# DMFX-2_v1_0.net
KiCad netlist of a schematic drawn in EAGLE
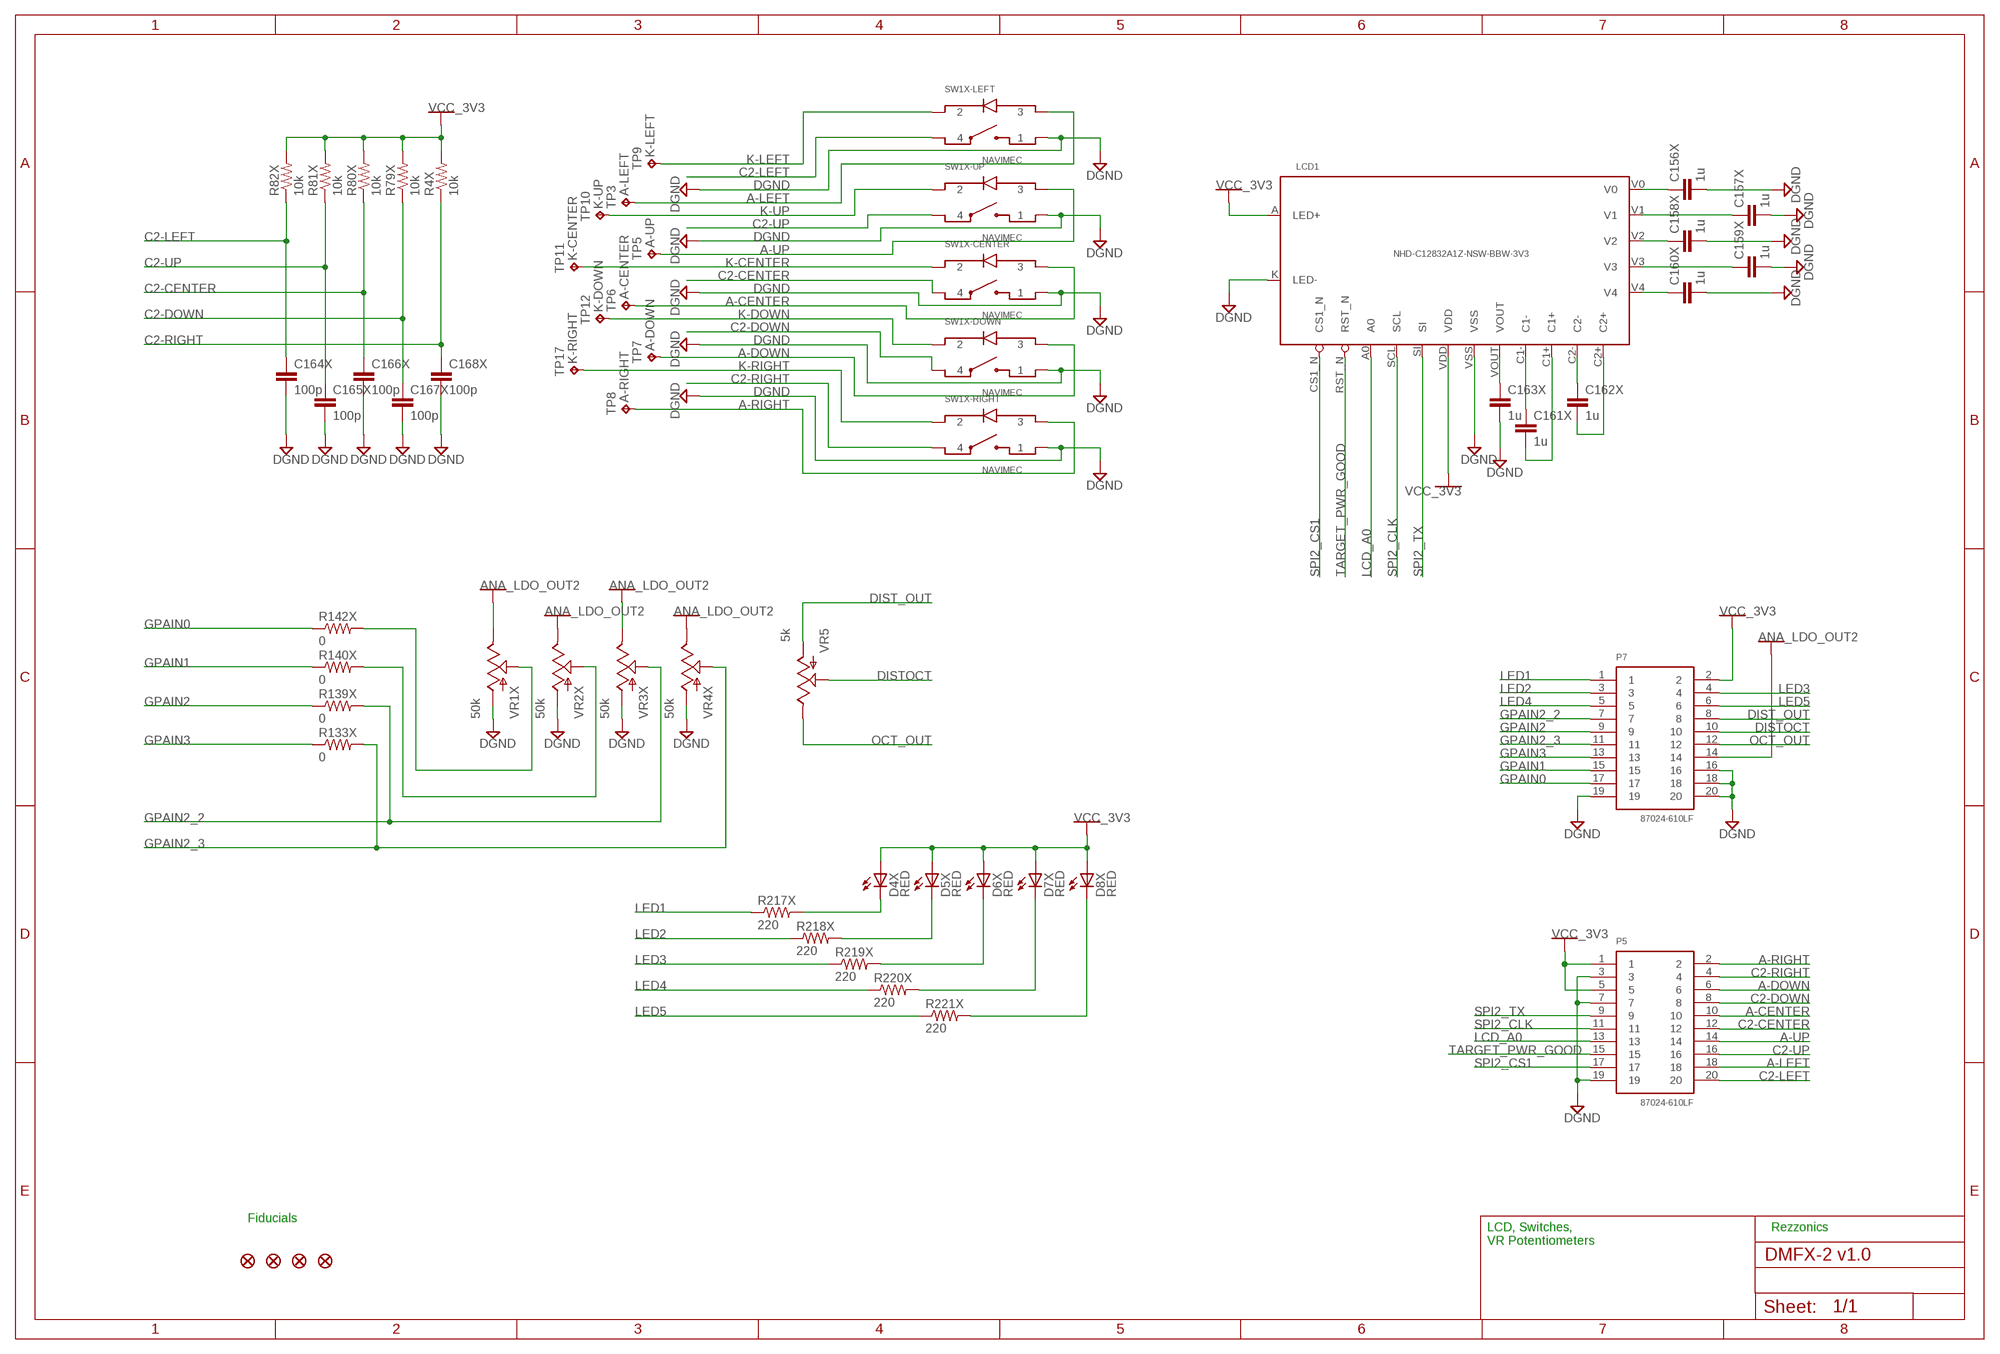
[diagram p0: schematic, sheet 1]

(export (version "E")
  (design (tool "Eeschema 10.0.6"))
  (components
    (comp (ref "C156X")
      (value "1u")
      (footprint "eagle-import:C0603K")
      (fields (field (name "MPN") "GRM188R7YA105KA12D"))
      (libsource (lib "eagle-import") (part "resistor_C-EUC0603K"))
    )
    (comp (ref "C157X")
      (value "1u")
      (footprint "eagle-import:C0603K")
      (fields (field (name "MPN") "GRM188R7YA105KA12D"))
      (libsource (lib "eagle-import") (part "resistor_C-EUC0603K"))
    )
    (comp (ref "C158X")
      (value "1u")
      (footprint "eagle-import:C0603K")
      (fields (field (name "MPN") "GRM188R7YA105KA12D"))
      (libsource (lib "eagle-import") (part "resistor_C-EUC0603K"))
    )
    (comp (ref "C159X")
      (value "1u")
      (footprint "eagle-import:C0603K")
      (fields (field (name "MPN") "GRM188R7YA105KA12D"))
      (libsource (lib "eagle-import") (part "resistor_C-EUC0603K"))
    )
    (comp (ref "C160X")
      (value "1u")
      (footprint "eagle-import:C0603K")
      (fields (field (name "MPN") "GRM188R7YA105KA12D"))
      (libsource (lib "eagle-import") (part "resistor_C-EUC0603K"))
    )
    (comp (ref "C161X")
      (value "1u")
      (footprint "eagle-import:C0603K")
      (fields (field (name "MPN") "GRM188R7YA105KA12D"))
      (libsource (lib "eagle-import") (part "resistor_C-EUC0603K"))
    )
    (comp (ref "C162X")
      (value "1u")
      (footprint "eagle-import:C0603K")
      (fields (field (name "MPN") "GRM188R7YA105KA12D"))
      (libsource (lib "eagle-import") (part "resistor_C-EUC0603K"))
    )
    (comp (ref "C163X")
      (value "1u")
      (footprint "eagle-import:C0603K")
      (fields (field (name "MPN") "GRM188R7YA105KA12D"))
      (libsource (lib "eagle-import") (part "resistor_C-EUC0603K"))
    )
    (comp (ref "C164X")
      (value "100p")
      (footprint "eagle-import:C0402")
      (fields (field (name "MPN") "GRM1555C1H101FA01J"))
      (libsource (lib "eagle-import") (part "C-EUC0402"))
    )
    (comp (ref "C165X")
      (value "100p")
      (footprint "eagle-import:C0402")
      (fields (field (name "MPN") "GRM1555C1H101FA01J"))
      (libsource (lib "eagle-import") (part "C-EUC0402"))
    )
    (comp (ref "C166X")
      (value "100p")
      (footprint "eagle-import:C0402")
      (fields (field (name "MPN") "GRM1555C1H101FA01J"))
      (libsource (lib "eagle-import") (part "C-EUC0402"))
    )
    (comp (ref "C167X")
      (value "100p")
      (footprint "eagle-import:C0402")
      (fields (field (name "MPN") "GRM1555C1H101FA01J"))
      (libsource (lib "eagle-import") (part "C-EUC0402"))
    )
    (comp (ref "C168X")
      (value "100p")
      (footprint "eagle-import:C0402")
      (fields (field (name "MPN") "GRM1555C1H101FA01J"))
      (libsource (lib "eagle-import") (part "C-EUC0402"))
    )
    (comp (ref "D4X")
      (value "RED")
      (footprint "eagle-import:LED3MM")
      (fields (field (name "MPN") "LTL-4222N"))
      (libsource (lib "eagle-import") (part "LED3MM"))
    )
    (comp (ref "D5X")
      (value "RED")
      (footprint "eagle-import:LED3MM")
      (fields (field (name "MPN") "LTL-4222N"))
      (libsource (lib "eagle-import") (part "LED3MM"))
    )
    (comp (ref "D6X")
      (value "RED")
      (footprint "eagle-import:LED3MM")
      (fields (field (name "MPN") "LTL-4222N"))
      (libsource (lib "eagle-import") (part "LED3MM"))
    )
    (comp (ref "D7X")
      (value "RED")
      (footprint "eagle-import:LED3MM")
      (fields (field (name "MPN") "LTL-4222N"))
      (libsource (lib "eagle-import") (part "LED3MM"))
    )
    (comp (ref "D8X")
      (value "RED")
      (footprint "eagle-import:LED3MM")
      (fields (field (name "MPN") "LTL-4222N"))
      (libsource (lib "eagle-import") (part "LED3MM"))
    )
    (comp (ref "JP2")
      (value "FIDUCIAL1X2.5")
      (footprint "eagle-import:FIDUCIAL-1X2.5")
      (libsource (lib "eagle-import") (part "FIDUCIAL1X2.5"))
    )
    (comp (ref "JP4")
      (value "FIDUCIAL1X2.5")
      (footprint "eagle-import:FIDUCIAL-1X2.5")
      (libsource (lib "eagle-import") (part "FIDUCIAL1X2.5"))
    )
    (comp (ref "JP5")
      (value "FIDUCIAL1X2.5")
      (footprint "eagle-import:FIDUCIAL-1X2.5")
      (libsource (lib "eagle-import") (part "FIDUCIAL1X2.5"))
    )
    (comp (ref "JP9")
      (value "FIDUCIAL1X2.5")
      (footprint "eagle-import:FIDUCIAL-1X2.5")
      (libsource (lib "eagle-import") (part "FIDUCIAL1X2.5"))
    )
    (comp (ref "LCD1")
      (value "NHD-C12832A1Z-NSW-BBW-3V3")
      (footprint "eagle-import:NHD-C12832A1Z")
      (libsource (lib "eagle-import") (part "NHD-C12832A1Z"))
    )
    (comp (ref "P5")
      (value "87024-610LF")
      (footprint "eagle-import:87022-110LF")
      (libsource (lib "eagle-import") (part "87022-110LF"))
    )
    (comp (ref "P7")
      (value "87024-610LF")
      (footprint "eagle-import:87022-110LF")
      (libsource (lib "eagle-import") (part "87022-110LF"))
    )
    (comp (ref "R4X")
      (value "10k")
      (footprint "eagle-import:0402-RES")
      (fields (field (name "MPN") "ERJ-2RKF1002X"))
      (libsource (lib "eagle-import") (part "RESISTOR0402-RES"))
    )
    (comp (ref "R79X")
      (value "10k")
      (footprint "eagle-import:0402-RES")
      (fields (field (name "MPN") "ERJ-2RKF1002X"))
      (libsource (lib "eagle-import") (part "RESISTOR0402-RES"))
    )
    (comp (ref "R80X")
      (value "10k")
      (footprint "eagle-import:0402-RES")
      (fields (field (name "MPN") "ERJ-2RKF1002X"))
      (libsource (lib "eagle-import") (part "RESISTOR0402-RES"))
    )
    (comp (ref "R81X")
      (value "10k")
      (footprint "eagle-import:0402-RES")
      (fields (field (name "MPN") "ERJ-2RKF1002X"))
      (libsource (lib "eagle-import") (part "RESISTOR0402-RES"))
    )
    (comp (ref "R82X")
      (value "10k")
      (footprint "eagle-import:0402-RES")
      (fields (field (name "MPN") "ERJ-2RKF1002X"))
      (libsource (lib "eagle-import") (part "RESISTOR0402-RES"))
    )
    (comp (ref "R133X")
      (value "0")
      (footprint "eagle-import:0402-RES")
      (fields (field (name "MPN") "ERJ-2GE0R00X"))
      (libsource (lib "eagle-import") (part "RESISTOR0402-RES"))
    )
    (comp (ref "R139X")
      (value "0")
      (footprint "eagle-import:0402-RES")
      (fields (field (name "MPN") "ERJ-2GE0R00X"))
      (libsource (lib "eagle-import") (part "RESISTOR0402-RES"))
    )
    (comp (ref "R140X")
      (value "0")
      (footprint "eagle-import:0402-RES")
      (fields (field (name "MPN") "ERJ-2GE0R00X"))
      (libsource (lib "eagle-import") (part "RESISTOR0402-RES"))
    )
    (comp (ref "R142X")
      (value "0")
      (footprint "eagle-import:0402-RES")
      (fields (field (name "MPN") "ERJ-2GE0R00X"))
      (libsource (lib "eagle-import") (part "RESISTOR0402-RES"))
    )
    (comp (ref "R217X")
      (value "220")
      (footprint "eagle-import:0402-RES")
      (fields (field (name "MPN") "ERJ-2RKF2200X"))
      (libsource (lib "eagle-import") (part "RESISTOR0402-RES"))
    )
    (comp (ref "R218X")
      (value "220")
      (footprint "eagle-import:0402-RES")
      (fields (field (name "MPN") "ERJ-2RKF2200X"))
      (libsource (lib "eagle-import") (part "RESISTOR0402-RES"))
    )
    (comp (ref "R219X")
      (value "220")
      (footprint "eagle-import:0402-RES")
      (fields (field (name "MPN") "ERJ-2RKF2200X"))
      (libsource (lib "eagle-import") (part "RESISTOR0402-RES"))
    )
    (comp (ref "R220X")
      (value "220")
      (footprint "eagle-import:0402-RES")
      (fields (field (name "MPN") "ERJ-2RKF2200X"))
      (libsource (lib "eagle-import") (part "RESISTOR0402-RES"))
    )
    (comp (ref "R221X")
      (value "220")
      (footprint "eagle-import:0402-RES")
      (fields (field (name "MPN") "ERJ-2RKF2200X"))
      (libsource (lib "eagle-import") (part "RESISTOR0402-RES"))
    )
    (comp (ref "SW1X")
      (value "NAVIMEC")
      (footprint "eagle-import:1ZW0913611806")
      (fields (field (name "MPN") "1ZW0913611806"))
      (libsource (lib "eagle-import") (part "1ZX16XLM13609"))
    )
    (comp (ref "TP3")
      (value "TPTP12R")
      (footprint "eagle-import:TP12R")
      (fields (field (name "TP_SIGNAL_NAME") "A-LEFT"))
      (libsource (lib "eagle-import") (part "TPTP12R"))
    )
    (comp (ref "TP5")
      (value "TPTP12R")
      (footprint "eagle-import:TP12R")
      (fields (field (name "TP_SIGNAL_NAME") "A-UP"))
      (libsource (lib "eagle-import") (part "TPTP12R"))
    )
    (comp (ref "TP6")
      (value "TPTP12R")
      (footprint "eagle-import:TP12R")
      (fields (field (name "TP_SIGNAL_NAME") "A-CENTER"))
      (libsource (lib "eagle-import") (part "TPTP12R"))
    )
    (comp (ref "TP7")
      (value "TPTP12R")
      (footprint "eagle-import:TP12R")
      (fields (field (name "TP_SIGNAL_NAME") "A-DOWN"))
      (libsource (lib "eagle-import") (part "TPTP12R"))
    )
    (comp (ref "TP8")
      (value "TPTP12R")
      (footprint "eagle-import:TP12R")
      (fields (field (name "TP_SIGNAL_NAME") "A-RIGHT"))
      (libsource (lib "eagle-import") (part "TPTP12R"))
    )
    (comp (ref "TP9")
      (value "TPTP12R")
      (footprint "eagle-import:TP12R")
      (fields (field (name "TP_SIGNAL_NAME") "K-LEFT"))
      (libsource (lib "eagle-import") (part "TPTP12R"))
    )
    (comp (ref "TP10")
      (value "TPTP12R")
      (footprint "eagle-import:TP12R")
      (fields (field (name "TP_SIGNAL_NAME") "K-UP"))
      (libsource (lib "eagle-import") (part "TPTP12R"))
    )
    (comp (ref "TP11")
      (value "TPTP12R")
      (footprint "eagle-import:TP12R")
      (fields (field (name "TP_SIGNAL_NAME") "K-CENTER"))
      (libsource (lib "eagle-import") (part "TPTP12R"))
    )
    (comp (ref "TP12")
      (value "TPTP12R")
      (footprint "eagle-import:TP12R")
      (fields (field (name "TP_SIGNAL_NAME") "K-DOWN"))
      (libsource (lib "eagle-import") (part "TPTP12R"))
    )
    (comp (ref "TP17")
      (value "TPTP12R")
      (footprint "eagle-import:TP12R")
      (fields (field (name "TP_SIGNAL_NAME") "K-RIGHT"))
      (libsource (lib "eagle-import") (part "TPTP12R"))
    )
    (comp (ref "VR1X")
      (value "50k")
      (footprint "eagle-import:ALPS_POT")
      (fields (field (name "MPN") "EVU-F2AF30B54"))
      (libsource (lib "eagle-import") (part "POT"))
    )
    (comp (ref "VR2X")
      (value "50k")
      (footprint "eagle-import:ALPS_POT")
      (fields (field (name "MPN") "EVU-F2AF30B54"))
      (libsource (lib "eagle-import") (part "POT"))
    )
    (comp (ref "VR3X")
      (value "50k")
      (footprint "eagle-import:ALPS_POT")
      (fields (field (name "MPN") "EVU-F2AF30B54"))
      (libsource (lib "eagle-import") (part "POT"))
    )
    (comp (ref "VR4X")
      (value "50k")
      (footprint "eagle-import:ALPS_POT")
      (fields (field (name "MPN") "EVU-F2AF30B54"))
      (libsource (lib "eagle-import") (part "POT"))
    )
    (comp (ref "VR5")
      (value "5k")
      (footprint "eagle-import:ALPS_POT")
      (fields (field (name "MPN") "EVU-F2AF30B53"))
      (libsource (lib "eagle-import") (part "POT"))
    )
  )
  (nets
    (net (code "1") (name "/A-CENTER") (class "Default")
      (node (ref "P5") (pin "10") (pinfunction "10_10") (pintype "passive"))
      (node (ref "SW1X") (pin "CENTER$3") (pinfunction "3_CENTER$3") (pintype "passive"))
      (node (ref "TP6") (pin "TP") (pinfunction "TP_TP") (pintype "input"))
    )
    (net (code "2") (name "/A-DOWN") (class "Default")
      (node (ref "P5") (pin "6") (pinfunction "6_6") (pintype "passive"))
      (node (ref "SW1X") (pin "DOWN$3") (pinfunction "3_DOWN$3") (pintype "passive"))
      (node (ref "TP7") (pin "TP") (pinfunction "TP_TP") (pintype "input"))
    )
    (net (code "3") (name "/A-LEFT") (class "Default")
      (node (ref "P5") (pin "18") (pinfunction "18_18") (pintype "passive"))
      (node (ref "SW1X") (pin "LEFT$3") (pinfunction "3_LEFT$3") (pintype "passive"))
      (node (ref "TP3") (pin "TP") (pinfunction "TP_TP") (pintype "input"))
    )
    (net (code "4") (name "/A-RIGHT") (class "Default")
      (node (ref "P5") (pin "2") (pinfunction "2_2") (pintype "passive"))
      (node (ref "SW1X") (pin "RIGHT$3") (pinfunction "3_RIGHT$3") (pintype "passive"))
      (node (ref "TP8") (pin "TP") (pinfunction "TP_TP") (pintype "input"))
    )
    (net (code "5") (name "/A-UP") (class "Default")
      (node (ref "P5") (pin "14") (pinfunction "14_14") (pintype "passive"))
      (node (ref "SW1X") (pin "UP$3") (pinfunction "3_UP$3") (pintype "passive"))
      (node (ref "TP5") (pin "TP") (pinfunction "TP_TP") (pintype "input"))
    )
    (net (code "6") (name "/C2-CENTER") (class "Default")
      (node (ref "C166X") (pin "1") (pinfunction "1_1") (pintype "passive"))
      (node (ref "P5") (pin "12") (pinfunction "12_12") (pintype "passive"))
      (node (ref "R80X") (pin "1") (pinfunction "1_1") (pintype "passive"))
      (node (ref "SW1X") (pin "CENTER$4") (pinfunction "4_CENTER$4") (pintype "passive"))
    )
    (net (code "7") (name "/C2-DOWN") (class "Default")
      (node (ref "C167X") (pin "1") (pinfunction "1_1") (pintype "passive"))
      (node (ref "P5") (pin "8") (pinfunction "8_8") (pintype "passive"))
      (node (ref "R79X") (pin "1") (pinfunction "1_1") (pintype "passive"))
      (node (ref "SW1X") (pin "DOWN$4") (pinfunction "4_DOWN$4") (pintype "passive"))
    )
    (net (code "8") (name "/C2-LEFT") (class "Default")
      (node (ref "C164X") (pin "1") (pinfunction "1_1") (pintype "passive"))
      (node (ref "P5") (pin "20") (pinfunction "20_20") (pintype "passive"))
      (node (ref "R82X") (pin "1") (pinfunction "1_1") (pintype "passive"))
      (node (ref "SW1X") (pin "LEFT$4") (pinfunction "4_LEFT$4") (pintype "passive"))
    )
    (net (code "9") (name "/C2-RIGHT") (class "Default")
      (node (ref "C168X") (pin "1") (pinfunction "1_1") (pintype "passive"))
      (node (ref "P5") (pin "4") (pinfunction "4_4") (pintype "passive"))
      (node (ref "R4X") (pin "1") (pinfunction "1_1") (pintype "passive"))
      (node (ref "SW1X") (pin "RIGHT$4") (pinfunction "4_RIGHT$4") (pintype "passive"))
    )
    (net (code "10") (name "/C2-UP") (class "Default")
      (node (ref "C165X") (pin "1") (pinfunction "1_1") (pintype "passive"))
      (node (ref "P5") (pin "16") (pinfunction "16_16") (pintype "passive"))
      (node (ref "R81X") (pin "1") (pinfunction "1_1") (pintype "passive"))
      (node (ref "SW1X") (pin "UP$4") (pinfunction "4_UP$4") (pintype "passive"))
    )
    (net (code "11") (name "/DISTOCT") (class "Default")
      (node (ref "P7") (pin "10") (pinfunction "10_10") (pintype "passive"))
      (node (ref "VR5") (pin "P$2") (pinfunction "S_P$2") (pintype "passive"))
    )
    (net (code "12") (name "/DIST_OUT") (class "Default")
      (node (ref "P7") (pin "8") (pinfunction "8_8") (pintype "passive"))
      (node (ref "VR5") (pin "P$3") (pinfunction "A_P$3") (pintype "passive"))
    )
    (net (code "13") (name "/GPAIN0") (class "Default")
      (node (ref "P7") (pin "17") (pinfunction "17_17") (pintype "passive"))
      (node (ref "R142X") (pin "1") (pinfunction "1_1") (pintype "passive"))
    )
    (net (code "14") (name "/GPAIN1") (class "Default")
      (node (ref "P7") (pin "15") (pinfunction "15_15") (pintype "passive"))
      (node (ref "R140X") (pin "1") (pinfunction "1_1") (pintype "passive"))
    )
    (net (code "15") (name "/GPAIN2") (class "Default")
      (node (ref "P7") (pin "9") (pinfunction "9_9") (pintype "passive"))
      (node (ref "R139X") (pin "1") (pinfunction "1_1") (pintype "passive"))
    )
    (net (code "16") (name "/GPAIN2_2") (class "Default")
      (node (ref "P7") (pin "7") (pinfunction "7_7") (pintype "passive"))
      (node (ref "R139X") (pin "2") (pinfunction "2_2") (pintype "passive"))
      (node (ref "VR3X") (pin "P$2") (pinfunction "S_P$2") (pintype "passive"))
    )
    (net (code "17") (name "/GPAIN2_3") (class "Default")
      (node (ref "P7") (pin "11") (pinfunction "11_11") (pintype "passive"))
      (node (ref "R133X") (pin "2") (pinfunction "2_2") (pintype "passive"))
      (node (ref "VR4X") (pin "P$2") (pinfunction "S_P$2") (pintype "passive"))
    )
    (net (code "18") (name "/GPAIN3") (class "Default")
      (node (ref "P7") (pin "13") (pinfunction "13_13") (pintype "passive"))
      (node (ref "R133X") (pin "1") (pinfunction "1_1") (pintype "passive"))
    )
    (net (code "19") (name "/K-CENTER") (class "Default")
      (node (ref "SW1X") (pin "CENTER$2") (pinfunction "2_CENTER$2") (pintype "passive"))
      (node (ref "TP11") (pin "TP") (pinfunction "TP_TP") (pintype "input"))
    )
    (net (code "20") (name "/K-DOWN") (class "Default")
      (node (ref "SW1X") (pin "DOWN$2") (pinfunction "2_DOWN$2") (pintype "passive"))
      (node (ref "TP12") (pin "TP") (pinfunction "TP_TP") (pintype "input"))
    )
    (net (code "21") (name "/K-LEFT") (class "Default")
      (node (ref "SW1X") (pin "LEFT$2") (pinfunction "2_LEFT$2") (pintype "passive"))
      (node (ref "TP9") (pin "TP") (pinfunction "TP_TP") (pintype "input"))
    )
    (net (code "22") (name "/K-RIGHT") (class "Default")
      (node (ref "SW1X") (pin "RIGHT$2") (pinfunction "2_RIGHT$2") (pintype "passive"))
      (node (ref "TP17") (pin "TP") (pinfunction "TP_TP") (pintype "input"))
    )
    (net (code "23") (name "/K-UP") (class "Default")
      (node (ref "SW1X") (pin "UP$2") (pinfunction "2_UP$2") (pintype "passive"))
      (node (ref "TP10") (pin "TP") (pinfunction "TP_TP") (pintype "input"))
    )
    (net (code "24") (name "/LCD_A0") (class "Default")
      (node (ref "LCD1") (pin "A0") (pinfunction "A0_A0") (pintype "input"))
      (node (ref "P5") (pin "13") (pinfunction "13_13") (pintype "passive"))
    )
    (net (code "25") (name "/LED1") (class "Default")
      (node (ref "P7") (pin "1") (pinfunction "1_1") (pintype "passive"))
      (node (ref "R217X") (pin "1") (pinfunction "1_1") (pintype "passive"))
    )
    (net (code "26") (name "/LED2") (class "Default")
      (node (ref "P7") (pin "3") (pinfunction "3_3") (pintype "passive"))
      (node (ref "R218X") (pin "1") (pinfunction "1_1") (pintype "passive"))
    )
    (net (code "27") (name "/LED3") (class "Default")
      (node (ref "P7") (pin "4") (pinfunction "4_4") (pintype "passive"))
      (node (ref "R219X") (pin "1") (pinfunction "1_1") (pintype "passive"))
    )
    (net (code "28") (name "/LED4") (class "Default")
      (node (ref "P7") (pin "5") (pinfunction "5_5") (pintype "passive"))
      (node (ref "R220X") (pin "1") (pinfunction "1_1") (pintype "passive"))
    )
    (net (code "29") (name "/LED5") (class "Default")
      (node (ref "P7") (pin "6") (pinfunction "6_6") (pintype "passive"))
      (node (ref "R221X") (pin "1") (pinfunction "1_1") (pintype "passive"))
    )
    (net (code "30") (name "/OCT_OUT") (class "Default")
      (node (ref "P7") (pin "12") (pinfunction "12_12") (pintype "passive"))
      (node (ref "VR5") (pin "P$1") (pinfunction "E_P$1") (pintype "passive"))
    )
    (net (code "31") (name "/SPI2_CLK") (class "Default")
      (node (ref "LCD1") (pin "SCL") (pinfunction "SCL_SCL") (pintype "input"))
      (node (ref "P5") (pin "11") (pinfunction "11_11") (pintype "passive"))
    )
    (net (code "32") (name "/SPI2_CS1") (class "Default")
      (node (ref "LCD1") (pin "CS1_N") (pinfunction "CS1_N_CS1_N") (pintype "input"))
      (node (ref "P5") (pin "17") (pinfunction "17_17") (pintype "passive"))
    )
    (net (code "33") (name "/SPI2_TX") (class "Default")
      (node (ref "LCD1") (pin "SI") (pinfunction "SI_SI") (pintype "input"))
      (node (ref "P5") (pin "9") (pinfunction "9_9") (pintype "passive"))
    )
    (net (code "34") (name "/TARGET_PWR_GOOD") (class "Default")
      (node (ref "LCD1") (pin "RST_N") (pinfunction "RST_N_RST_N") (pintype "input"))
      (node (ref "P5") (pin "15") (pinfunction "15_15") (pintype "passive"))
    )
    (net (code "35") (name "ANA_LDO_OUT2") (class "Default")
      (node (ref "P7") (pin "14") (pinfunction "14_14") (pintype "passive"))
      (node (ref "VR1X") (pin "P$1") (pinfunction "E_P$1") (pintype "passive"))
      (node (ref "VR2X") (pin "P$1") (pinfunction "E_P$1") (pintype "passive"))
      (node (ref "VR3X") (pin "P$1") (pinfunction "E_P$1") (pintype "passive"))
      (node (ref "VR4X") (pin "P$1") (pinfunction "E_P$1") (pintype "passive"))
    )
    (net (code "36") (name "DGND") (class "Default")
      (node (ref "C156X") (pin "2") (pinfunction "2_2") (pintype "passive"))
      (node (ref "C157X") (pin "2") (pinfunction "2_2") (pintype "passive"))
      (node (ref "C158X") (pin "2") (pinfunction "2_2") (pintype "passive"))
      (node (ref "C159X") (pin "2") (pinfunction "2_2") (pintype "passive"))
      (node (ref "C160X") (pin "2") (pinfunction "2_2") (pintype "passive"))
      (node (ref "C163X") (pin "2") (pinfunction "2_2") (pintype "passive"))
      (node (ref "C164X") (pin "2") (pinfunction "2_2") (pintype "passive"))
      (node (ref "C165X") (pin "2") (pinfunction "2_2") (pintype "passive"))
      (node (ref "C166X") (pin "2") (pinfunction "2_2") (pintype "passive"))
      (node (ref "C167X") (pin "2") (pinfunction "2_2") (pintype "passive"))
      (node (ref "C168X") (pin "2") (pinfunction "2_2") (pintype "passive"))
      (node (ref "LCD1") (pin "K") (pinfunction "LED-_K") (pintype "power_in"))
      (node (ref "LCD1") (pin "VSS") (pinfunction "VSS_VSS") (pintype "power_in"))
      (node (ref "P5") (pin "19") (pinfunction "19_19") (pintype "passive"))
      (node (ref "P5") (pin "3") (pinfunction "3_3") (pintype "passive"))
      (node (ref "P5") (pin "7") (pinfunction "7_7") (pintype "passive"))
      (node (ref "P7") (pin "16") (pinfunction "16_16") (pintype "passive"))
      (node (ref "P7") (pin "18") (pinfunction "18_18") (pintype "passive"))
      (node (ref "P7") (pin "19") (pinfunction "19_19") (pintype "passive"))
      (node (ref "P7") (pin "20") (pinfunction "20_20") (pintype "passive"))
      (node (ref "SW1X") (pin "CENTER$1") (pinfunction "1_CENTER$1") (pintype "passive"))
      (node (ref "SW1X") (pin "DOWN$1") (pinfunction "1_DOWN$1") (pintype "passive"))
      (node (ref "SW1X") (pin "LEFT$1") (pinfunction "1_LEFT$1") (pintype "passive"))
      (node (ref "SW1X") (pin "RIGHT$1") (pinfunction "1_RIGHT$1") (pintype "passive"))
      (node (ref "SW1X") (pin "UP$1") (pinfunction "1_UP$1") (pintype "passive"))
      (node (ref "VR1X") (pin "P$3") (pinfunction "A_P$3") (pintype "passive"))
      (node (ref "VR2X") (pin "P$3") (pinfunction "A_P$3") (pintype "passive"))
      (node (ref "VR3X") (pin "P$3") (pinfunction "A_P$3") (pintype "passive"))
      (node (ref "VR4X") (pin "P$3") (pinfunction "A_P$3") (pintype "passive"))
    )
    (net (code "37") (name "Net-(C156X-Pad1)") (class "Default")
      (node (ref "C156X") (pin "1") (pinfunction "1_1") (pintype "passive"))
      (node (ref "LCD1") (pin "V0") (pinfunction "V0_V0") (pintype "power_in"))
    )
    (net (code "38") (name "Net-(C157X-Pad1)") (class "Default")
      (node (ref "C157X") (pin "1") (pinfunction "1_1") (pintype "passive"))
      (node (ref "LCD1") (pin "V1") (pinfunction "V1_V1") (pintype "power_in"))
    )
    (net (code "39") (name "Net-(C158X-Pad1)") (class "Default")
      (node (ref "C158X") (pin "1") (pinfunction "1_1") (pintype "passive"))
      (node (ref "LCD1") (pin "V2") (pinfunction "V2_V2") (pintype "power_in"))
    )
    (net (code "40") (name "Net-(C159X-Pad1)") (class "Default")
      (node (ref "C159X") (pin "1") (pinfunction "1_1") (pintype "passive"))
      (node (ref "LCD1") (pin "V3") (pinfunction "V3_V3") (pintype "power_in"))
    )
    (net (code "41") (name "Net-(C160X-Pad1)") (class "Default")
      (node (ref "C160X") (pin "1") (pinfunction "1_1") (pintype "passive"))
      (node (ref "LCD1") (pin "V4") (pinfunction "V4_V4") (pintype "power_in"))
    )
    (net (code "42") (name "Net-(C161X-Pad1)") (class "Default")
      (node (ref "C161X") (pin "1") (pinfunction "1_1") (pintype "passive"))
      (node (ref "LCD1") (pin "C1-") (pinfunction "C1-_C1-") (pintype "power_in"))
    )
    (net (code "43") (name "Net-(C161X-Pad2)") (class "Default")
      (node (ref "C161X") (pin "2") (pinfunction "2_2") (pintype "passive"))
      (node (ref "LCD1") (pin "C1+") (pinfunction "C1+_C1+") (pintype "power_in"))
    )
    (net (code "44") (name "Net-(C162X-Pad1)") (class "Default")
      (node (ref "C162X") (pin "1") (pinfunction "1_1") (pintype "passive"))
      (node (ref "LCD1") (pin "C2-") (pinfunction "C2-_C2-") (pintype "power_in"))
    )
    (net (code "45") (name "Net-(C162X-Pad2)") (class "Default")
      (node (ref "C162X") (pin "2") (pinfunction "2_2") (pintype "passive"))
      (node (ref "LCD1") (pin "C2+") (pinfunction "C2+_C2+") (pintype "power_in"))
    )
    (net (code "46") (name "Net-(C163X-Pad1)") (class "Default")
      (node (ref "C163X") (pin "1") (pinfunction "1_1") (pintype "passive"))
      (node (ref "LCD1") (pin "VOUT") (pinfunction "VOUT_VOUT") (pintype "power_in"))
    )
    (net (code "47") (name "Net-(D4X-C)") (class "Default")
      (node (ref "D4X") (pin "K") (pinfunction "C_K") (pintype "passive"))
      (node (ref "R217X") (pin "2") (pinfunction "2_2") (pintype "passive"))
    )
    (net (code "48") (name "Net-(D5X-C)") (class "Default")
      (node (ref "D5X") (pin "K") (pinfunction "C_K") (pintype "passive"))
      (node (ref "R218X") (pin "2") (pinfunction "2_2") (pintype "passive"))
    )
    (net (code "49") (name "Net-(D6X-C)") (class "Default")
      (node (ref "D6X") (pin "K") (pinfunction "C_K") (pintype "passive"))
      (node (ref "R219X") (pin "2") (pinfunction "2_2") (pintype "passive"))
    )
    (net (code "50") (name "Net-(D7X-C)") (class "Default")
      (node (ref "D7X") (pin "K") (pinfunction "C_K") (pintype "passive"))
      (node (ref "R220X") (pin "2") (pinfunction "2_2") (pintype "passive"))
    )
    (net (code "51") (name "Net-(D8X-C)") (class "Default")
      (node (ref "D8X") (pin "K") (pinfunction "C_K") (pintype "passive"))
      (node (ref "R221X") (pin "2") (pinfunction "2_2") (pintype "passive"))
    )
    (net (code "52") (name "Net-(VR1X-S)") (class "Default")
      (node (ref "R142X") (pin "2") (pinfunction "2_2") (pintype "passive"))
      (node (ref "VR1X") (pin "P$2") (pinfunction "S_P$2") (pintype "passive"))
    )
    (net (code "53") (name "Net-(VR2X-S)") (class "Default")
      (node (ref "R140X") (pin "2") (pinfunction "2_2") (pintype "passive"))
      (node (ref "VR2X") (pin "P$2") (pinfunction "S_P$2") (pintype "passive"))
    )
    (net (code "54") (name "VCC_3V3") (class "Default")
      (node (ref "D4X") (pin "A") (pinfunction "A_A") (pintype "passive"))
      (node (ref "D5X") (pin "A") (pinfunction "A_A") (pintype "passive"))
      (node (ref "D6X") (pin "A") (pinfunction "A_A") (pintype "passive"))
      (node (ref "D7X") (pin "A") (pinfunction "A_A") (pintype "passive"))
      (node (ref "D8X") (pin "A") (pinfunction "A_A") (pintype "passive"))
      (node (ref "LCD1") (pin "A") (pinfunction "LED+_A") (pintype "power_in"))
      (node (ref "LCD1") (pin "VDD") (pinfunction "VDD_VDD") (pintype "power_in"))
      (node (ref "P5") (pin "1") (pinfunction "1_1") (pintype "passive"))
      (node (ref "P5") (pin "5") (pinfunction "5_5") (pintype "passive"))
      (node (ref "P7") (pin "2") (pinfunction "2_2") (pintype "passive"))
      (node (ref "R4X") (pin "2") (pinfunction "2_2") (pintype "passive"))
      (node (ref "R79X") (pin "2") (pinfunction "2_2") (pintype "passive"))
      (node (ref "R80X") (pin "2") (pinfunction "2_2") (pintype "passive"))
      (node (ref "R81X") (pin "2") (pinfunction "2_2") (pintype "passive"))
      (node (ref "R82X") (pin "2") (pinfunction "2_2") (pintype "passive"))
    )
  )
)
